# brain_rev_3.net
KiCad netlist of a schematic drawn in EAGLE
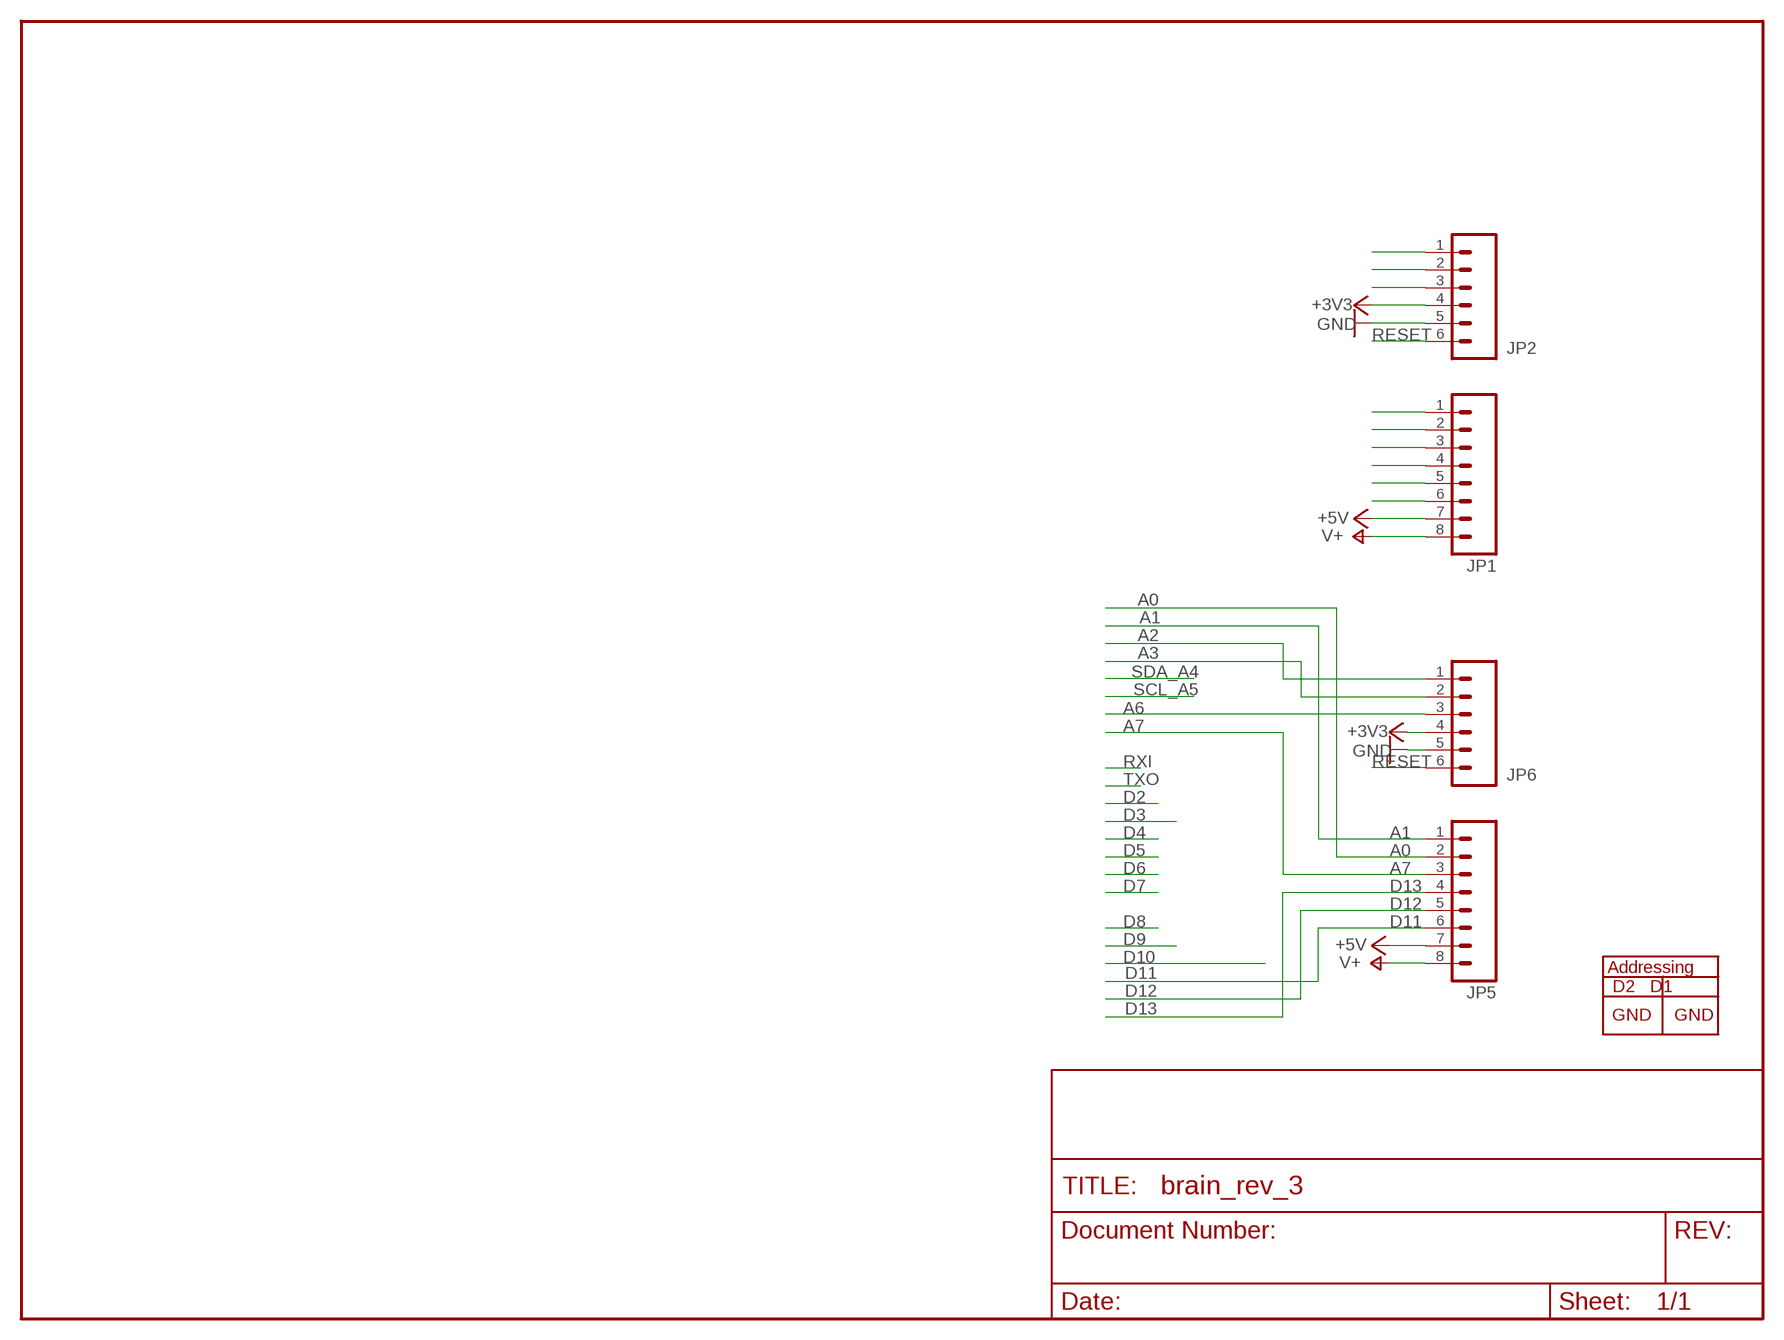
[diagram p0: schematic, sheet 1]

(export (version "E")
  (design (tool "Eeschema 10.0.6"))
  (components
    (comp (ref "JP1")
      (value "M081X08")
      (footprint "eagle-import:1X08")
      (libsource (lib "eagle-import") (part "M081X08"))
    )
    (comp (ref "JP2")
      (value "M06SIP")
      (footprint "eagle-import:1X06")
      (libsource (lib "eagle-import") (part "M06SIP"))
    )
    (comp (ref "JP5")
      (value "M081X08")
      (footprint "eagle-import:1X08")
      (libsource (lib "eagle-import") (part "M081X08"))
    )
    (comp (ref "JP6")
      (value "M06SIP")
      (footprint "eagle-import:1X06")
      (libsource (lib "eagle-import") (part "M06SIP"))
    )
  )
  (nets
    (net (code "1") (name "+3V3") (class "Default")
      (node (ref "JP2") (pin "4") (pinfunction "4_4") (pintype "passive"))
      (node (ref "JP6") (pin "4") (pinfunction "4_4") (pintype "passive"))
    )
    (net (code "2") (name "+5V") (class "Default")
      (node (ref "JP1") (pin "7") (pinfunction "7_7") (pintype "passive"))
      (node (ref "JP5") (pin "7") (pinfunction "7_7") (pintype "passive"))
    )
    (net (code "3") (name "/A0") (class "Default")
      (node (ref "JP5") (pin "2") (pinfunction "2_2") (pintype "passive"))
    )
    (net (code "4") (name "/A1") (class "Default")
      (node (ref "JP5") (pin "1") (pinfunction "1_1") (pintype "passive"))
    )
    (net (code "5") (name "/A2") (class "Default")
      (node (ref "JP6") (pin "1") (pinfunction "1_1") (pintype "passive"))
    )
    (net (code "6") (name "/A3") (class "Default")
      (node (ref "JP6") (pin "2") (pinfunction "2_2") (pintype "passive"))
    )
    (net (code "7") (name "/A6") (class "Default")
      (node (ref "JP6") (pin "3") (pinfunction "3_3") (pintype "passive"))
    )
    (net (code "8") (name "/A7") (class "Default")
      (node (ref "JP5") (pin "3") (pinfunction "3_3") (pintype "passive"))
    )
    (net (code "18") (name "/D11") (class "Default")
      (node (ref "JP5") (pin "6") (pinfunction "6_6") (pintype "passive"))
    )
    (net (code "19") (name "/D12") (class "Default")
      (node (ref "JP5") (pin "5") (pinfunction "5_5") (pintype "passive"))
    )
    (net (code "20") (name "/D13") (class "Default")
      (node (ref "JP5") (pin "4") (pinfunction "4_4") (pintype "passive"))
    )
    (net (code "21") (name "/RESET") (class "Default")
      (node (ref "JP2") (pin "6") (pinfunction "6_6") (pintype "passive"))
      (node (ref "JP6") (pin "6") (pinfunction "6_6") (pintype "passive"))
    )
    (net (code "26") (name "GND") (class "Default")
      (node (ref "JP2") (pin "5") (pinfunction "5_5") (pintype "passive"))
      (node (ref "JP6") (pin "5") (pinfunction "5_5") (pintype "passive"))
    )
    (net (code "27") (name "V+") (class "Default")
      (node (ref "JP1") (pin "8") (pinfunction "8_8") (pintype "passive"))
      (node (ref "JP5") (pin "8") (pinfunction "8_8") (pintype "passive"))
    )
    (net (code "28") (name "unconnected-(JP1-Pad1)") (class "Default")
      (node (ref "JP1") (pin "1") (pinfunction "1_1") (pintype "passive"))
    )
    (net (code "29") (name "unconnected-(JP1-Pad2)") (class "Default")
      (node (ref "JP1") (pin "2") (pinfunction "2_2") (pintype "passive"))
    )
    (net (code "30") (name "unconnected-(JP1-Pad3)") (class "Default")
      (node (ref "JP1") (pin "3") (pinfunction "3_3") (pintype "passive"))
    )
    (net (code "31") (name "unconnected-(JP1-Pad4)") (class "Default")
      (node (ref "JP1") (pin "4") (pinfunction "4_4") (pintype "passive"))
    )
    (net (code "32") (name "unconnected-(JP1-Pad5)") (class "Default")
      (node (ref "JP1") (pin "5") (pinfunction "5_5") (pintype "passive"))
    )
    (net (code "33") (name "unconnected-(JP1-Pad6)") (class "Default")
      (node (ref "JP1") (pin "6") (pinfunction "6_6") (pintype "passive"))
    )
    (net (code "34") (name "unconnected-(JP2-Pad1)") (class "Default")
      (node (ref "JP2") (pin "1") (pinfunction "1_1") (pintype "passive"))
    )
    (net (code "35") (name "unconnected-(JP2-Pad2)") (class "Default")
      (node (ref "JP2") (pin "2") (pinfunction "2_2") (pintype "passive"))
    )
    (net (code "36") (name "unconnected-(JP2-Pad3)") (class "Default")
      (node (ref "JP2") (pin "3") (pinfunction "3_3") (pintype "passive"))
    )
  )
)
